# Sch_mcu_brd_pwr.net
KiCad netlist of a schematic drawn in Altium Designer
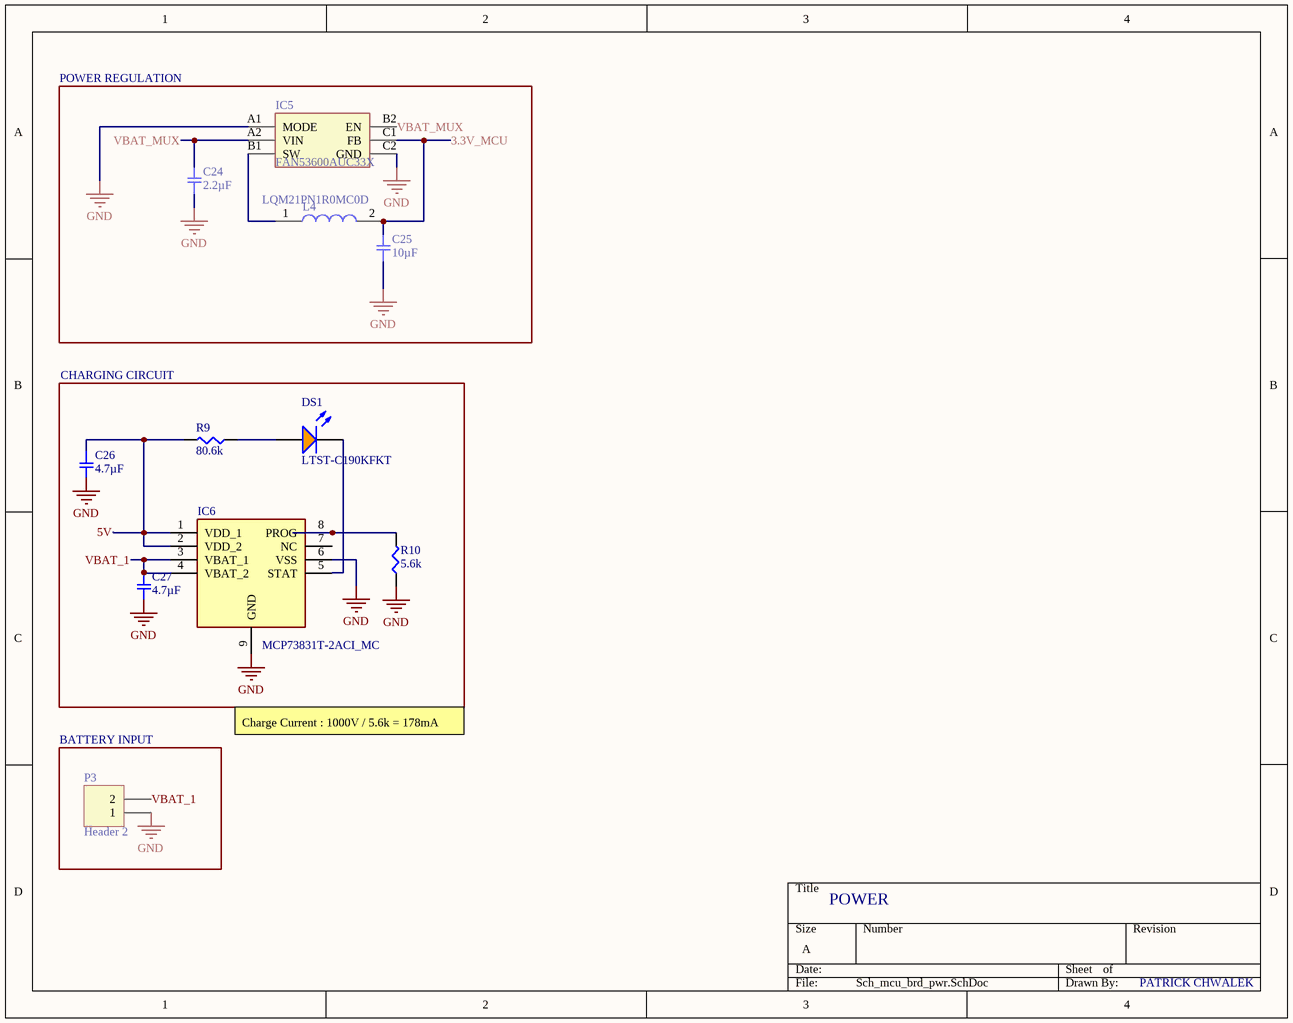
[diagram p0: Sch_mcu_brd_pwr.SchDoc]

(export (version "E")
  (design (tool "Eeschema 10.0.6"))
  (components
    (comp (ref "C24")
      (value "2.2µF")
      (footprint "SMD-0402C")
      (description "CAP CER 2.2UF 6.3V X5R 0402")
      (fields
        (field (name "DIGI-KEY PART NUMBER") "490-4519-1-ND")
        (field (name "PART NUMBER") "GRM155R60J225ME15D")
      )
      (libsource (lib "capacitor_murata_0402") (part "GRM155R60J225ME15D"))
    )
    (comp (ref "C25")
      (value "10µF")
      (footprint "SMD-0603C")
      (description "CAP CER 10UF 6.3V X5R 0603")
      (fields
        (field (name "DIGI-KEY PART NUMBER") "490-3896-1-ND")
        (field (name "PART NUMBER") "GRM188R60J106ME47D")
      )
      (libsource (lib "capacitor_murata_0603") (part "GRM188R60J106ME47D"))
    )
    (comp (ref "C26")
      (value "4.7µF")
      (footprint "SMD-0402C")
      (description "CAP CER 4.7UF 4V X5R 0402")
      (fields
        (field (name "DIGI-KEY PART NUMBER") "490-13231-1-ND")
        (field (name "PART NUMBER") "GRM153R60G475ME15D")
      )
      (libsource (lib "capacitor_murata_0402") (part "GRM153R60G475ME15D"))
    )
    (comp (ref "C27")
      (value "4.7µF")
      (footprint "SMD-0402C")
      (description "CAP CER 4.7UF 4V X5R 0402")
      (fields
        (field (name "DIGI-KEY PART NUMBER") "490-13231-1-ND")
        (field (name "PART NUMBER") "GRM153R60G475ME15D")
      )
      (libsource (lib "capacitor_murata_0402") (part "GRM153R60G475ME15D"))
    )
    (comp (ref "DS1")
      (value "LTST-C190KFKT")
      (footprint "LTST-C190KFKT_V")
      (description "LED Uni-Color Orange, 75 mW, 30 mA, -35 to 85 degC, 2-Pin SMD, RoHS, Tape and Reel")
      (fields (field (name "TOLERANCE") "1%"))
      (libsource (lib "Altium Content Vault") (part "LED-ORANGE-AK-2"))
    )
    (comp (ref "IC5")
      (value "FAN53600AUC33X")
      (footprint "SamacSys:BGA6C40P2X3_86X116X62")
      (description "Integrated Circuit")
      (fields (field (name "MOUSER PART NUMBER") "512-FAN53600AUC33X"))
      (libsource (lib "SamacSys") (part "FAN53600AUC33X"))
    )
    (comp (ref "IC6")
      (value "MCP73831T-2ACI_MC")
      (footprint "SON50P300X200X100-9N-D")
      (description "Integrated Circuit")
      (fields
        (field (name "MANUFACTURER_PART_NUMBER") "MCP73831T-2ACI/MC")
        (field (name "MOUSER PART NUMBER") "579-MCP73831T-2ACIMC")
      )
      (libsource (lib "SamacSys") (part "MCP73831T-2ACI_MC"))
    )
    (comp (ref "L4")
      (value "LQM21PN1R0MC0D")
      (footprint "SamacSys:INDC2012X55N")
      (description "Inductor")
      (fields
        (field (name "MOUSER PART NUMBER") "81-LQM21PN1R0MC0D")
        (field (name "RS PART NUMBER") "7926388")
      )
      (libsource (lib "SamacSys") (part "LQM21PN1R0MC0D"))
    )
    (comp (ref "P3")
      (value "Header 2")
      (footprint "HDR1X2")
      (description "Header, 2-Pin")
      (fields (field (name "PUBLISHER") "Altium Limited"))
      (libsource (lib "Miscellaneous Connectors") (part "Header 2"))
    )
    (comp (ref "R9")
      (value "80.6k")
      (footprint "SMD-0402-RES")
      (description "RES SMD 80.6K OHM 1% 1/10W 0402")
      (fields
        (field (name "PART NUMBER") "ERJ-2RKF8062X")
        (field (name "DIGI-KEY PART NUMBER") "P80.6KLCT-ND")
      )
      (libsource (lib "Panasonic_ERJ_0402") (part "ERJ-2RKF8062X"))
    )
    (comp (ref "R10")
      (value "5.6k")
      (footprint "SMD-0402-RES")
      (description "RES SMD 5.6K OHM 5% 1/10W 0402")
      (fields (field (name "PART NUMBER") "ERJ-2GEJ562X") (field (name "DIGI-KEY PART NUMBER") "P5.6KJCT-ND"))
      (libsource (lib "Panasonic_ERJ_0402") (part "ERJ-2GEJ562X"))
    )
  )
  (nets
    (net (code "1") (name "/3.3V_MCU") (class "Default")
      (node (ref "C25") (pin "2") (pinfunction "2_2") (pintype "passive"))
      (node (ref "IC5") (pin "C1") (pinfunction "FB_C1") (pintype "passive"))
      (node (ref "L4") (pin "2") (pinfunction "2_2") (pintype "passive"))
    )
    (net (code "2") (name "/5V") (class "Default")
      (node (ref "C26") (pin "1") (pinfunction "1_1") (pintype "passive"))
      (node (ref "IC6") (pin "1") (pinfunction "VDD_1_1") (pintype "passive"))
      (node (ref "IC6") (pin "2") (pinfunction "VDD_2_2") (pintype "passive"))
      (node (ref "R9") (pin "2") (pinfunction "2_2") (pintype "passive"))
    )
    (net (code "3") (name "/VBAT_1") (class "Default")
      (node (ref "C27") (pin "1") (pinfunction "1_1") (pintype "passive"))
      (node (ref "IC6") (pin "3") (pinfunction "VBAT_1_3") (pintype "passive"))
      (node (ref "IC6") (pin "4") (pinfunction "VBAT_2_4") (pintype "passive"))
      (node (ref "P3") (pin "2") (pinfunction "2_2") (pintype "passive"))
    )
    (net (code "4") (name "/VBAT_MUX") (class "Default")
      (node (ref "C24") (pin "2") (pinfunction "2_2") (pintype "passive"))
      (node (ref "IC5") (pin "A2") (pinfunction "VIN_A2") (pintype "passive"))
      (node (ref "IC5") (pin "B2") (pinfunction "EN_B2") (pintype "passive"))
    )
    (net (code "5") (name "GND") (class "Default")
      (node (ref "C24") (pin "1") (pinfunction "1_1") (pintype "passive"))
      (node (ref "C25") (pin "1") (pinfunction "1_1") (pintype "passive"))
      (node (ref "C26") (pin "2") (pinfunction "2_2") (pintype "passive"))
      (node (ref "C27") (pin "2") (pinfunction "2_2") (pintype "passive"))
      (node (ref "IC5") (pin "A1") (pinfunction "MODE_A1") (pintype "passive"))
      (node (ref "IC5") (pin "C2") (pinfunction "GND_C2") (pintype "passive"))
      (node (ref "IC6") (pin "6") (pinfunction "VSS_6") (pintype "passive"))
      (node (ref "IC6") (pin "9") (pinfunction "GND_9") (pintype "passive"))
      (node (ref "P3") (pin "1") (pinfunction "1_1") (pintype "passive"))
      (node (ref "R10") (pin "1") (pinfunction "1_1") (pintype "passive"))
    )
    (net (code "6") (name "Net-(DS1-A)") (class "Default")
      (node (ref "DS1") (pin "1") (pinfunction "A_1") (pintype "passive"))
      (node (ref "R9") (pin "1") (pinfunction "1_1") (pintype "passive"))
    )
    (net (code "7") (name "Net-(DS1-K)") (class "Default")
      (node (ref "DS1") (pin "2") (pinfunction "K_2") (pintype "passive"))
      (node (ref "IC6") (pin "5") (pinfunction "STAT_5") (pintype "passive"))
    )
    (net (code "8") (name "Net-(IC5-SW)") (class "Default")
      (node (ref "IC5") (pin "B1") (pinfunction "SW_B1") (pintype "passive"))
      (node (ref "L4") (pin "1") (pinfunction "1_1") (pintype "passive"))
    )
    (net (code "9") (name "Net-(IC6-PROG)") (class "Default")
      (node (ref "IC6") (pin "8") (pinfunction "PROG_8") (pintype "passive"))
      (node (ref "R10") (pin "2") (pinfunction "2_2") (pintype "passive"))
    )
    (net (code "10") (name "unconnected-(IC6-NC-Pad7)") (class "Default")
      (node (ref "IC6") (pin "7") (pinfunction "NC_7") (pintype "passive"))
    )
  )
)
